# sensor.net
KiCad netlist of a schematic drawn in EAGLE
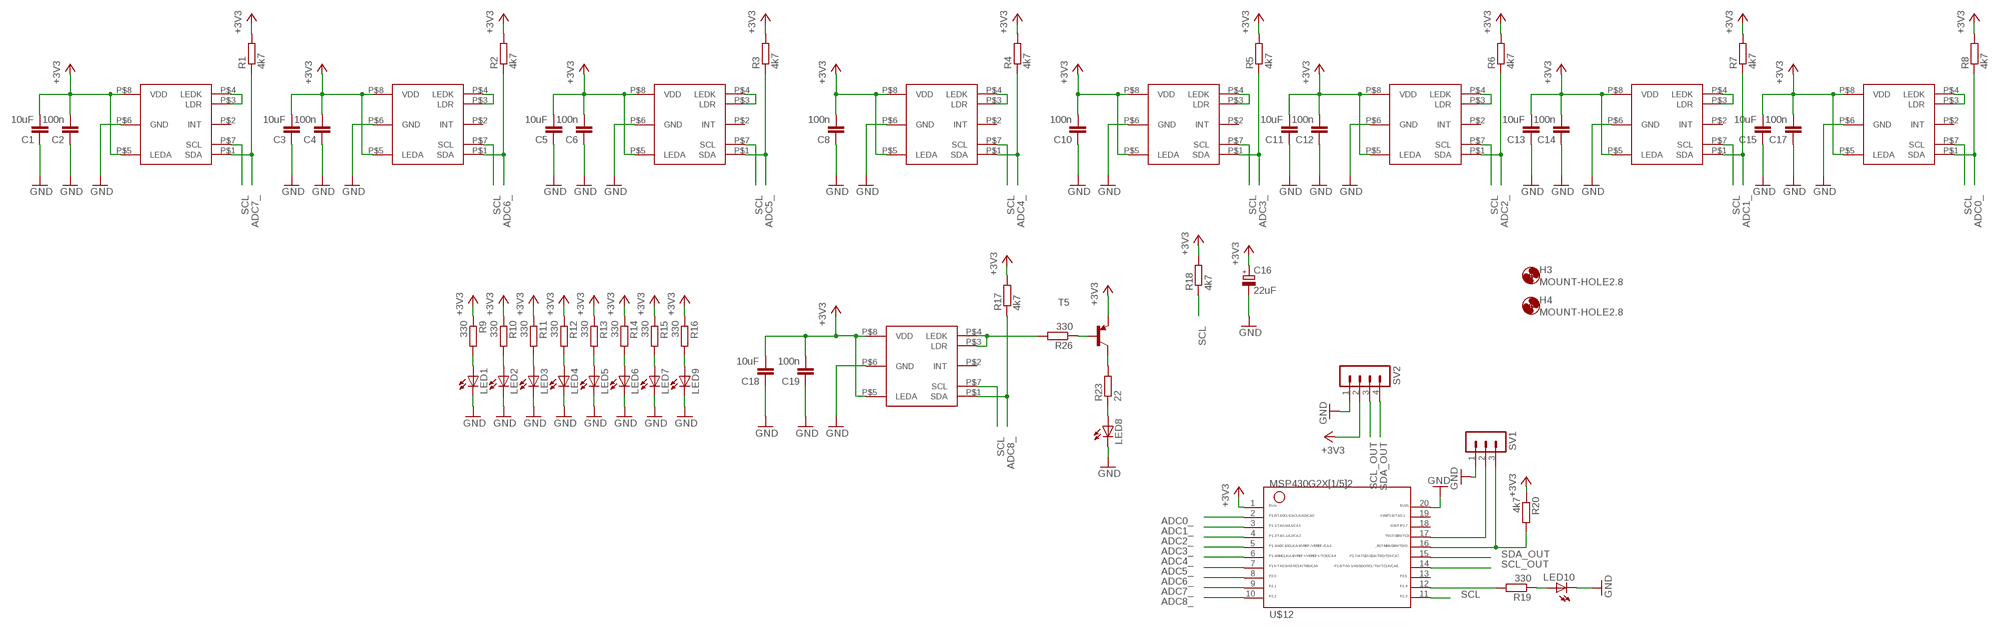
[diagram p0: schematic, sheet 1]

(export (version "E")
  (design (tool "Eeschema 10.0.6"))
  (components
    (comp (ref "C1")
      (value "10uF")
      (footprint "eagle-import:C0805")
      (libsource (lib "eagle-import") (part "C-EUC0805"))
    )
    (comp (ref "C2")
      (value "100n")
      (footprint "eagle-import:C0805")
      (libsource (lib "eagle-import") (part "C-EUC0805"))
    )
    (comp (ref "C3")
      (value "10uF")
      (footprint "eagle-import:C0805")
      (libsource (lib "eagle-import") (part "C-EUC0805"))
    )
    (comp (ref "C4")
      (value "100n")
      (footprint "eagle-import:C0805")
      (libsource (lib "eagle-import") (part "C-EUC0805"))
    )
    (comp (ref "C5")
      (value "10uF")
      (footprint "eagle-import:C0805")
      (libsource (lib "eagle-import") (part "C-EUC0805"))
    )
    (comp (ref "C6")
      (value "100n")
      (footprint "eagle-import:C0805")
      (libsource (lib "eagle-import") (part "C-EUC0805"))
    )
    (comp (ref "C8")
      (value "100n")
      (footprint "eagle-import:C0805")
      (libsource (lib "eagle-import") (part "C-EUC0805"))
    )
    (comp (ref "C10")
      (value "100n")
      (footprint "eagle-import:C0805")
      (libsource (lib "eagle-import") (part "C-EUC0805"))
    )
    (comp (ref "C11")
      (value "10uF")
      (footprint "eagle-import:C0805")
      (libsource (lib "eagle-import") (part "C-EUC0805"))
    )
    (comp (ref "C12")
      (value "100n")
      (footprint "eagle-import:C0805")
      (libsource (lib "eagle-import") (part "C-EUC0805"))
    )
    (comp (ref "C13")
      (value "10uF")
      (footprint "eagle-import:C0805")
      (libsource (lib "eagle-import") (part "C-EUC0805"))
    )
    (comp (ref "C14")
      (value "100n")
      (footprint "eagle-import:C0805")
      (libsource (lib "eagle-import") (part "C-EUC0805"))
    )
    (comp (ref "C15")
      (value "10uF")
      (footprint "eagle-import:C0805")
      (libsource (lib "eagle-import") (part "C-EUC0805"))
    )
    (comp (ref "C16")
      (value "22uF")
      (footprint "eagle-import:153CLV-0505")
      (libsource (lib "eagle-import") (part "CPOL-EU153CLV-0505"))
    )
    (comp (ref "C17")
      (value "100n")
      (footprint "eagle-import:C0805")
      (libsource (lib "eagle-import") (part "C-EUC0805"))
    )
    (comp (ref "C18")
      (value "10uF")
      (footprint "eagle-import:C0805")
      (libsource (lib "eagle-import") (part "C-EUC0805"))
    )
    (comp (ref "C19")
      (value "100n")
      (footprint "eagle-import:C0805")
      (libsource (lib "eagle-import") (part "C-EUC0805"))
    )
    (comp (ref "H3")
      (value "MOUNT-HOLE2.8")
      (footprint "eagle-import:2,8")
      (libsource (lib "eagle-import") (part "MOUNT-HOLE2.8"))
    )
    (comp (ref "H4")
      (value "MOUNT-HOLE2.8")
      (footprint "eagle-import:2,8")
      (libsource (lib "eagle-import") (part "MOUNT-HOLE2.8"))
    )
    (comp (ref "LED1")
      (value "LEDCHIPLED_1206")
      (footprint "eagle-import:CHIPLED_1206")
      (libsource (lib "eagle-import") (part "my_parts_LEDCHIPLED_1206"))
    )
    (comp (ref "LED2")
      (value "LEDCHIPLED_1206")
      (footprint "eagle-import:CHIPLED_1206")
      (libsource (lib "eagle-import") (part "my_parts_LEDCHIPLED_1206"))
    )
    (comp (ref "LED3")
      (value "LEDCHIPLED_1206")
      (footprint "eagle-import:CHIPLED_1206")
      (libsource (lib "eagle-import") (part "my_parts_LEDCHIPLED_1206"))
    )
    (comp (ref "LED4")
      (value "LEDCHIPLED_1206")
      (footprint "eagle-import:CHIPLED_1206")
      (libsource (lib "eagle-import") (part "my_parts_LEDCHIPLED_1206"))
    )
    (comp (ref "LED5")
      (value "LEDCHIPLED_1206")
      (footprint "eagle-import:CHIPLED_1206")
      (libsource (lib "eagle-import") (part "my_parts_LEDCHIPLED_1206"))
    )
    (comp (ref "LED6")
      (value "LEDCHIPLED_1206")
      (footprint "eagle-import:CHIPLED_1206")
      (libsource (lib "eagle-import") (part "my_parts_LEDCHIPLED_1206"))
    )
    (comp (ref "LED7")
      (value "LEDCHIPLED_1206")
      (footprint "eagle-import:CHIPLED_1206")
      (libsource (lib "eagle-import") (part "my_parts_LEDCHIPLED_1206"))
    )
    (comp (ref "LED8")
      (value "LED5MM")
      (footprint "eagle-import:LED5MM")
      (libsource (lib "eagle-import") (part "LED5MM"))
    )
    (comp (ref "LED9")
      (value "LEDCHIPLED_1206")
      (footprint "eagle-import:CHIPLED_1206")
      (libsource (lib "eagle-import") (part "my_parts_LEDCHIPLED_1206"))
    )
    (comp (ref "LED10")
      (value "LEDCHIPLED_1206")
      (footprint "eagle-import:CHIPLED_1206")
      (libsource (lib "eagle-import") (part "my_parts_LEDCHIPLED_1206"))
    )
    (comp (ref "R1")
      (value "4k7")
      (footprint "eagle-import:M0805")
      (libsource (lib "eagle-import") (part "R-EU_M0805"))
    )
    (comp (ref "R2")
      (value "4k7")
      (footprint "eagle-import:M0805")
      (libsource (lib "eagle-import") (part "R-EU_M0805"))
    )
    (comp (ref "R3")
      (value "4k7")
      (footprint "eagle-import:M0805")
      (libsource (lib "eagle-import") (part "R-EU_M0805"))
    )
    (comp (ref "R4")
      (value "4k7")
      (footprint "eagle-import:M0805")
      (libsource (lib "eagle-import") (part "R-EU_M0805"))
    )
    (comp (ref "R5")
      (value "4k7")
      (footprint "eagle-import:M0805")
      (libsource (lib "eagle-import") (part "R-EU_M0805"))
    )
    (comp (ref "R6")
      (value "4k7")
      (footprint "eagle-import:M0805")
      (libsource (lib "eagle-import") (part "R-EU_M0805"))
    )
    (comp (ref "R7")
      (value "4k7")
      (footprint "eagle-import:M0805")
      (libsource (lib "eagle-import") (part "R-EU_M0805"))
    )
    (comp (ref "R8")
      (value "4k7")
      (footprint "eagle-import:M0805")
      (libsource (lib "eagle-import") (part "R-EU_M0805"))
    )
    (comp (ref "R9")
      (value "330")
      (footprint "eagle-import:M0805")
      (libsource (lib "eagle-import") (part "R-EU_M0805"))
    )
    (comp (ref "R10")
      (value "330")
      (footprint "eagle-import:M0805")
      (libsource (lib "eagle-import") (part "R-EU_M0805"))
    )
    (comp (ref "R11")
      (value "330")
      (footprint "eagle-import:M0805")
      (libsource (lib "eagle-import") (part "R-EU_M0805"))
    )
    (comp (ref "R12")
      (value "330")
      (footprint "eagle-import:M0805")
      (libsource (lib "eagle-import") (part "R-EU_M0805"))
    )
    (comp (ref "R13")
      (value "330")
      (footprint "eagle-import:M0805")
      (libsource (lib "eagle-import") (part "R-EU_M0805"))
    )
    (comp (ref "R14")
      (value "330")
      (footprint "eagle-import:M0805")
      (libsource (lib "eagle-import") (part "R-EU_M0805"))
    )
    (comp (ref "R15")
      (value "330")
      (footprint "eagle-import:M0805")
      (libsource (lib "eagle-import") (part "R-EU_M0805"))
    )
    (comp (ref "R16")
      (value "330")
      (footprint "eagle-import:M0805")
      (libsource (lib "eagle-import") (part "R-EU_M0805"))
    )
    (comp (ref "R17")
      (value "4k7")
      (footprint "eagle-import:M0805")
      (libsource (lib "eagle-import") (part "R-EU_M0805"))
    )
    (comp (ref "R18")
      (value "4k7")
      (footprint "eagle-import:M0805")
      (libsource (lib "eagle-import") (part "R-EU_M0805"))
    )
    (comp (ref "R19")
      (value "330")
      (footprint "eagle-import:M0805")
      (libsource (lib "eagle-import") (part "R-EU_M0805"))
    )
    (comp (ref "R20")
      (value "4k7")
      (footprint "eagle-import:M0805")
      (libsource (lib "eagle-import") (part "R-EU_M0805"))
    )
    (comp (ref "R23")
      (value "22")
      (footprint "eagle-import:M0805")
      (libsource (lib "eagle-import") (part "R-EU_M0805"))
    )
    (comp (ref "R26")
      (value "330")
      (footprint "eagle-import:M0805")
      (libsource (lib "eagle-import") (part "R-EU_M0805"))
    )
    (comp (ref "SV1")
      (value "MA03-1")
      (footprint "eagle-import:MA03-1")
      (libsource (lib "eagle-import") (part "MA03-1"))
    )
    (comp (ref "SV2")
      (value "MA04-1")
      (footprint "eagle-import:MA04-1")
      (libsource (lib "eagle-import") (part "MA04-1"))
    )
    (comp (ref "T5")
      (value "BC857A-PNP-SOT23-BEC")
      (footprint "eagle-import:SOT23-BEC")
      (libsource (lib "eagle-import") (part "-PNP-SOT23-BECBC857A"))
    )
    (comp (ref "U$1")
      (value "APDS9950")
      (footprint "eagle-import:APDS9950")
      (libsource (lib "eagle-import") (part "APDS9950"))
    )
    (comp (ref "U$2")
      (value "APDS9950_EDGE")
      (footprint "eagle-import:APDS9950_EDGE")
      (libsource (lib "eagle-import") (part "APDS9950_EDGE"))
    )
    (comp (ref "U$4")
      (value "APDS9950")
      (footprint "eagle-import:APDS9950")
      (libsource (lib "eagle-import") (part "APDS9950"))
    )
    (comp (ref "U$5")
      (value "APDS9950")
      (footprint "eagle-import:APDS9950")
      (libsource (lib "eagle-import") (part "APDS9950"))
    )
    (comp (ref "U$6")
      (value "APDS9950")
      (footprint "eagle-import:APDS9950")
      (libsource (lib "eagle-import") (part "APDS9950"))
    )
    (comp (ref "U$7")
      (value "APDS9950")
      (footprint "eagle-import:APDS9950")
      (libsource (lib "eagle-import") (part "APDS9950"))
    )
    (comp (ref "U$8")
      (value "APDS9950")
      (footprint "eagle-import:APDS9950")
      (libsource (lib "eagle-import") (part "APDS9950"))
    )
    (comp (ref "U$9")
      (value "APDS9950")
      (footprint "eagle-import:APDS9950")
      (libsource (lib "eagle-import") (part "APDS9950"))
    )
    (comp (ref "U$10")
      (value "APDS9950")
      (footprint "eagle-import:APDS9950")
      (libsource (lib "eagle-import") (part "APDS9950"))
    )
    (comp (ref "U$12")
      (value "G2X[1/5]2---PW20")
      (footprint "eagle-import:PW20")
      (libsource (lib "eagle-import") (part "G2X[1/5]2---PW20"))
    )
  )
  (nets
    (net (code "1") (name "+3V3") (class "Default")
      (node (ref "C1") (pin "2") (pinfunction "2_2") (pintype "passive"))
      (node (ref "C10") (pin "2") (pinfunction "2_2") (pintype "passive"))
      (node (ref "C11") (pin "2") (pinfunction "2_2") (pintype "passive"))
      (node (ref "C12") (pin "2") (pinfunction "2_2") (pintype "passive"))
      (node (ref "C13") (pin "2") (pinfunction "2_2") (pintype "passive"))
      (node (ref "C14") (pin "2") (pinfunction "2_2") (pintype "passive"))
      (node (ref "C15") (pin "2") (pinfunction "2_2") (pintype "passive"))
      (node (ref "C16") (pin "+") (pinfunction "+_+") (pintype "passive"))
      (node (ref "C17") (pin "2") (pinfunction "2_2") (pintype "passive"))
      (node (ref "C18") (pin "2") (pinfunction "2_2") (pintype "passive"))
      (node (ref "C19") (pin "2") (pinfunction "2_2") (pintype "passive"))
      (node (ref "C2") (pin "2") (pinfunction "2_2") (pintype "passive"))
      (node (ref "C3") (pin "2") (pinfunction "2_2") (pintype "passive"))
      (node (ref "C4") (pin "2") (pinfunction "2_2") (pintype "passive"))
      (node (ref "C5") (pin "2") (pinfunction "2_2") (pintype "passive"))
      (node (ref "C6") (pin "2") (pinfunction "2_2") (pintype "passive"))
      (node (ref "C8") (pin "2") (pinfunction "2_2") (pintype "passive"))
      (node (ref "R1") (pin "2") (pinfunction "2_2") (pintype "passive"))
      (node (ref "R10") (pin "1") (pinfunction "1_1") (pintype "passive"))
      (node (ref "R11") (pin "1") (pinfunction "1_1") (pintype "passive"))
      (node (ref "R12") (pin "1") (pinfunction "1_1") (pintype "passive"))
      (node (ref "R13") (pin "1") (pinfunction "1_1") (pintype "passive"))
      (node (ref "R14") (pin "1") (pinfunction "1_1") (pintype "passive"))
      (node (ref "R15") (pin "1") (pinfunction "1_1") (pintype "passive"))
      (node (ref "R16") (pin "1") (pinfunction "1_1") (pintype "passive"))
      (node (ref "R17") (pin "2") (pinfunction "2_2") (pintype "passive"))
      (node (ref "R18") (pin "2") (pinfunction "2_2") (pintype "passive"))
      (node (ref "R2") (pin "2") (pinfunction "2_2") (pintype "passive"))
      (node (ref "R20") (pin "1") (pinfunction "1_1") (pintype "passive"))
      (node (ref "R3") (pin "2") (pinfunction "2_2") (pintype "passive"))
      (node (ref "R4") (pin "2") (pinfunction "2_2") (pintype "passive"))
      (node (ref "R5") (pin "2") (pinfunction "2_2") (pintype "passive"))
      (node (ref "R6") (pin "2") (pinfunction "2_2") (pintype "passive"))
      (node (ref "R7") (pin "2") (pinfunction "2_2") (pintype "passive"))
      (node (ref "R8") (pin "2") (pinfunction "2_2") (pintype "passive"))
      (node (ref "R9") (pin "1") (pinfunction "1_1") (pintype "passive"))
      (node (ref "SV2") (pin "2") (pinfunction "2_2") (pintype "passive"))
      (node (ref "T5") (pin "E") (pinfunction "E_E") (pintype "passive"))
      (node (ref "U$1") (pin "P$5") (pinfunction "LEDA_P$5") (pintype "bidirectional"))
      (node (ref "U$1") (pin "P$8") (pinfunction "VDD_P$8") (pintype "bidirectional"))
      (node (ref "U$10") (pin "P$5") (pinfunction "LEDA_P$5") (pintype "bidirectional"))
      (node (ref "U$10") (pin "P$8") (pinfunction "VDD_P$8") (pintype "bidirectional"))
      (node (ref "U$12") (pin "1") (pinfunction "1_1") (pintype "bidirectional"))
      (node (ref "U$2") (pin "P$5") (pinfunction "LEDA_P$5") (pintype "bidirectional"))
      (node (ref "U$2") (pin "P$8") (pinfunction "VDD_P$8") (pintype "bidirectional"))
      (node (ref "U$4") (pin "P$5") (pinfunction "LEDA_P$5") (pintype "bidirectional"))
      (node (ref "U$4") (pin "P$8") (pinfunction "VDD_P$8") (pintype "bidirectional"))
      (node (ref "U$5") (pin "P$5") (pinfunction "LEDA_P$5") (pintype "bidirectional"))
      (node (ref "U$5") (pin "P$8") (pinfunction "VDD_P$8") (pintype "bidirectional"))
      (node (ref "U$6") (pin "P$5") (pinfunction "LEDA_P$5") (pintype "bidirectional"))
      (node (ref "U$6") (pin "P$8") (pinfunction "VDD_P$8") (pintype "bidirectional"))
      (node (ref "U$7") (pin "P$5") (pinfunction "LEDA_P$5") (pintype "bidirectional"))
      (node (ref "U$7") (pin "P$8") (pinfunction "VDD_P$8") (pintype "bidirectional"))
      (node (ref "U$8") (pin "P$5") (pinfunction "LEDA_P$5") (pintype "bidirectional"))
      (node (ref "U$8") (pin "P$8") (pinfunction "VDD_P$8") (pintype "bidirectional"))
      (node (ref "U$9") (pin "P$5") (pinfunction "LEDA_P$5") (pintype "bidirectional"))
      (node (ref "U$9") (pin "P$8") (pinfunction "VDD_P$8") (pintype "bidirectional"))
    )
    (net (code "2") (name "/ADC0_") (class "Default")
      (node (ref "R8") (pin "1") (pinfunction "1_1") (pintype "passive"))
      (node (ref "U$10") (pin "P$1") (pinfunction "SDA_P$1") (pintype "bidirectional"))
      (node (ref "U$12") (pin "2") (pinfunction "2_2") (pintype "bidirectional"))
    )
    (net (code "3") (name "/ADC1_") (class "Default")
      (node (ref "R7") (pin "1") (pinfunction "1_1") (pintype "passive"))
      (node (ref "U$12") (pin "3") (pinfunction "3_3") (pintype "bidirectional"))
      (node (ref "U$9") (pin "P$1") (pinfunction "SDA_P$1") (pintype "bidirectional"))
    )
    (net (code "4") (name "/ADC2_") (class "Default")
      (node (ref "R6") (pin "1") (pinfunction "1_1") (pintype "passive"))
      (node (ref "U$12") (pin "4") (pinfunction "4_4") (pintype "bidirectional"))
      (node (ref "U$8") (pin "P$1") (pinfunction "SDA_P$1") (pintype "bidirectional"))
    )
    (net (code "5") (name "/ADC3_") (class "Default")
      (node (ref "R5") (pin "1") (pinfunction "1_1") (pintype "passive"))
      (node (ref "U$12") (pin "5") (pinfunction "5_5") (pintype "bidirectional"))
      (node (ref "U$7") (pin "P$1") (pinfunction "SDA_P$1") (pintype "bidirectional"))
    )
    (net (code "6") (name "/ADC4_") (class "Default")
      (node (ref "R4") (pin "1") (pinfunction "1_1") (pintype "passive"))
      (node (ref "U$12") (pin "6") (pinfunction "6_6") (pintype "bidirectional"))
      (node (ref "U$6") (pin "P$1") (pinfunction "SDA_P$1") (pintype "bidirectional"))
    )
    (net (code "7") (name "/ADC5_") (class "Default")
      (node (ref "R3") (pin "1") (pinfunction "1_1") (pintype "passive"))
      (node (ref "U$12") (pin "7") (pinfunction "7_7") (pintype "bidirectional"))
      (node (ref "U$5") (pin "P$1") (pinfunction "SDA_P$1") (pintype "bidirectional"))
    )
    (net (code "8") (name "/ADC6_") (class "Default")
      (node (ref "R2") (pin "1") (pinfunction "1_1") (pintype "passive"))
      (node (ref "U$12") (pin "8") (pinfunction "8_8") (pintype "bidirectional"))
      (node (ref "U$4") (pin "P$1") (pinfunction "SDA_P$1") (pintype "bidirectional"))
    )
    (net (code "9") (name "/ADC7_") (class "Default")
      (node (ref "R1") (pin "1") (pinfunction "1_1") (pintype "passive"))
      (node (ref "U$1") (pin "P$1") (pinfunction "SDA_P$1") (pintype "bidirectional"))
      (node (ref "U$12") (pin "9") (pinfunction "9_9") (pintype "bidirectional"))
    )
    (net (code "10") (name "/ADC8_") (class "Default")
      (node (ref "R17") (pin "1") (pinfunction "1_1") (pintype "passive"))
      (node (ref "U$12") (pin "10") (pinfunction "10_10") (pintype "bidirectional"))
      (node (ref "U$2") (pin "P$1") (pinfunction "SDA_P$1") (pintype "bidirectional"))
    )
    (net (code "11") (name "/SCL") (class "Default")
      (node (ref "R18") (pin "1") (pinfunction "1_1") (pintype "passive"))
      (node (ref "U$1") (pin "P$7") (pinfunction "SCL_P$7") (pintype "bidirectional"))
      (node (ref "U$10") (pin "P$7") (pinfunction "SCL_P$7") (pintype "bidirectional"))
      (node (ref "U$12") (pin "11") (pinfunction "11_11") (pintype "bidirectional"))
      (node (ref "U$2") (pin "P$7") (pinfunction "SCL_P$7") (pintype "bidirectional"))
      (node (ref "U$4") (pin "P$7") (pinfunction "SCL_P$7") (pintype "bidirectional"))
      (node (ref "U$5") (pin "P$7") (pinfunction "SCL_P$7") (pintype "bidirectional"))
      (node (ref "U$6") (pin "P$7") (pinfunction "SCL_P$7") (pintype "bidirectional"))
      (node (ref "U$7") (pin "P$7") (pinfunction "SCL_P$7") (pintype "bidirectional"))
      (node (ref "U$8") (pin "P$7") (pinfunction "SCL_P$7") (pintype "bidirectional"))
      (node (ref "U$9") (pin "P$7") (pinfunction "SCL_P$7") (pintype "bidirectional"))
    )
    (net (code "12") (name "/SCL_OUT") (class "Default")
      (node (ref "SV2") (pin "3") (pinfunction "3_3") (pintype "passive"))
      (node (ref "U$12") (pin "14") (pinfunction "14_14") (pintype "bidirectional"))
    )
    (net (code "13") (name "/SDA_OUT") (class "Default")
      (node (ref "SV2") (pin "4") (pinfunction "4_4") (pintype "passive"))
      (node (ref "U$12") (pin "15") (pinfunction "15_15") (pintype "bidirectional"))
    )
    (net (code "14") (name "GND") (class "Default")
      (node (ref "C1") (pin "1") (pinfunction "1_1") (pintype "passive"))
      (node (ref "C10") (pin "1") (pinfunction "1_1") (pintype "passive"))
      (node (ref "C11") (pin "1") (pinfunction "1_1") (pintype "passive"))
      (node (ref "C12") (pin "1") (pinfunction "1_1") (pintype "passive"))
      (node (ref "C13") (pin "1") (pinfunction "1_1") (pintype "passive"))
      (node (ref "C14") (pin "1") (pinfunction "1_1") (pintype "passive"))
      (node (ref "C15") (pin "1") (pinfunction "1_1") (pintype "passive"))
      (node (ref "C16") (pin "-") (pinfunction "-_-") (pintype "passive"))
      (node (ref "C17") (pin "1") (pinfunction "1_1") (pintype "passive"))
      (node (ref "C18") (pin "1") (pinfunction "1_1") (pintype "passive"))
      (node (ref "C19") (pin "1") (pinfunction "1_1") (pintype "passive"))
      (node (ref "C2") (pin "1") (pinfunction "1_1") (pintype "passive"))
      (node (ref "C3") (pin "1") (pinfunction "1_1") (pintype "passive"))
      (node (ref "C4") (pin "1") (pinfunction "1_1") (pintype "passive"))
      (node (ref "C5") (pin "1") (pinfunction "1_1") (pintype "passive"))
      (node (ref "C6") (pin "1") (pinfunction "1_1") (pintype "passive"))
      (node (ref "C8") (pin "1") (pinfunction "1_1") (pintype "passive"))
      (node (ref "LED1") (pin "C") (pinfunction "C_C") (pintype "passive"))
      (node (ref "LED10") (pin "C") (pinfunction "C_C") (pintype "passive"))
      (node (ref "LED2") (pin "C") (pinfunction "C_C") (pintype "passive"))
      (node (ref "LED3") (pin "C") (pinfunction "C_C") (pintype "passive"))
      (node (ref "LED4") (pin "C") (pinfunction "C_C") (pintype "passive"))
      (node (ref "LED5") (pin "C") (pinfunction "C_C") (pintype "passive"))
      (node (ref "LED6") (pin "C") (pinfunction "C_C") (pintype "passive"))
      (node (ref "LED7") (pin "C") (pinfunction "C_C") (pintype "passive"))
      (node (ref "LED8") (pin "K") (pinfunction "C_K") (pintype "passive"))
      (node (ref "LED9") (pin "C") (pinfunction "C_C") (pintype "passive"))
      (node (ref "SV1") (pin "1") (pinfunction "1_1") (pintype "passive"))
      (node (ref "SV2") (pin "1") (pinfunction "1_1") (pintype "passive"))
      (node (ref "U$1") (pin "P$6") (pinfunction "GND_P$6") (pintype "bidirectional"))
      (node (ref "U$10") (pin "P$6") (pinfunction "GND_P$6") (pintype "bidirectional"))
      (node (ref "U$12") (pin "20") (pinfunction "20_20") (pintype "bidirectional"))
      (node (ref "U$2") (pin "P$6") (pinfunction "GND_P$6") (pintype "bidirectional"))
      (node (ref "U$4") (pin "P$6") (pinfunction "GND_P$6") (pintype "bidirectional"))
      (node (ref "U$5") (pin "P$6") (pinfunction "GND_P$6") (pintype "bidirectional"))
      (node (ref "U$6") (pin "P$6") (pinfunction "GND_P$6") (pintype "bidirectional"))
      (node (ref "U$7") (pin "P$6") (pinfunction "GND_P$6") (pintype "bidirectional"))
      (node (ref "U$8") (pin "P$6") (pinfunction "GND_P$6") (pintype "bidirectional"))
      (node (ref "U$9") (pin "P$6") (pinfunction "GND_P$6") (pintype "bidirectional"))
    )
    (net (code "15") (name "Net-(LED1-PadA)") (class "Default")
      (node (ref "LED1") (pin "A") (pinfunction "A_A") (pintype "passive"))
      (node (ref "R9") (pin "2") (pinfunction "2_2") (pintype "passive"))
    )
    (net (code "16") (name "Net-(LED2-PadA)") (class "Default")
      (node (ref "LED2") (pin "A") (pinfunction "A_A") (pintype "passive"))
      (node (ref "R10") (pin "2") (pinfunction "2_2") (pintype "passive"))
    )
    (net (code "17") (name "Net-(LED3-PadA)") (class "Default")
      (node (ref "LED3") (pin "A") (pinfunction "A_A") (pintype "passive"))
      (node (ref "R11") (pin "2") (pinfunction "2_2") (pintype "passive"))
    )
    (net (code "18") (name "Net-(LED4-PadA)") (class "Default")
      (node (ref "LED4") (pin "A") (pinfunction "A_A") (pintype "passive"))
      (node (ref "R12") (pin "2") (pinfunction "2_2") (pintype "passive"))
    )
    (net (code "19") (name "Net-(LED5-PadA)") (class "Default")
      (node (ref "LED5") (pin "A") (pinfunction "A_A") (pintype "passive"))
      (node (ref "R13") (pin "2") (pinfunction "2_2") (pintype "passive"))
    )
    (net (code "20") (name "Net-(LED6-PadA)") (class "Default")
      (node (ref "LED6") (pin "A") (pinfunction "A_A") (pintype "passive"))
      (node (ref "R14") (pin "2") (pinfunction "2_2") (pintype "passive"))
    )
    (net (code "21") (name "Net-(LED7-PadA)") (class "Default")
      (node (ref "LED7") (pin "A") (pinfunction "A_A") (pintype "passive"))
      (node (ref "R15") (pin "2") (pinfunction "2_2") (pintype "passive"))
    )
    (net (code "22") (name "Net-(LED8-PadA)") (class "Default")
      (node (ref "LED8") (pin "A") (pinfunction "A_A") (pintype "passive"))
      (node (ref "R23") (pin "1") (pinfunction "1_1") (pintype "passive"))
    )
    (net (code "23") (name "Net-(LED9-PadA)") (class "Default")
      (node (ref "LED9") (pin "A") (pinfunction "A_A") (pintype "passive"))
      (node (ref "R16") (pin "2") (pinfunction "2_2") (pintype "passive"))
    )
    (net (code "24") (name "Net-(LED10-PadA)") (class "Default")
      (node (ref "LED10") (pin "A") (pinfunction "A_A") (pintype "passive"))
      (node (ref "R19") (pin "1") (pinfunction "1_1") (pintype "passive"))
    )
    (net (code "25") (name "Net-(R19-Pad2)") (class "Default")
      (node (ref "R19") (pin "2") (pinfunction "2_2") (pintype "passive"))
      (node (ref "U$12") (pin "12") (pinfunction "12_12") (pintype "bidirectional"))
    )
    (net (code "26") (name "Net-(R20-Pad2)") (class "Default")
      (node (ref "R20") (pin "2") (pinfunction "2_2") (pintype "passive"))
      (node (ref "SV1") (pin "3") (pinfunction "3_3") (pintype "passive"))
      (node (ref "U$12") (pin "16") (pinfunction "16_16") (pintype "bidirectional"))
    )
    (net (code "27") (name "Net-(R23-Pad2)") (class "Default")
      (node (ref "R23") (pin "2") (pinfunction "2_2") (pintype "passive"))
      (node (ref "T5") (pin "C") (pinfunction "C_C") (pintype "passive"))
    )
    (net (code "28") (name "Net-(R26-Pad1)") (class "Default")
      (node (ref "R26") (pin "1") (pinfunction "1_1") (pintype "passive"))
      (node (ref "T5") (pin "B") (pinfunction "B_B") (pintype "passive"))
    )
    (net (code "29") (name "Net-(SV1-Pad2)") (class "Default")
      (node (ref "SV1") (pin "2") (pinfunction "2_2") (pintype "passive"))
      (node (ref "U$12") (pin "17") (pinfunction "17_17") (pintype "bidirectional"))
    )
    (net (code "30") (name "Net-(U$1-LDR)") (class "Default")
      (node (ref "U$1") (pin "P$3") (pinfunction "LDR_P$3") (pintype "bidirectional"))
      (node (ref "U$1") (pin "P$4") (pinfunction "LEDK_P$4") (pintype "bidirectional"))
    )
    (net (code "31") (name "Net-(U$2-LDR)") (class "Default")
      (node (ref "R26") (pin "2") (pinfunction "2_2") (pintype "passive"))
      (node (ref "U$2") (pin "P$3") (pinfunction "LDR_P$3") (pintype "bidirectional"))
      (node (ref "U$2") (pin "P$4") (pinfunction "LEDK_P$4") (pintype "bidirectional"))
    )
    (net (code "32") (name "Net-(U$4-LDR)") (class "Default")
      (node (ref "U$4") (pin "P$3") (pinfunction "LDR_P$3") (pintype "bidirectional"))
      (node (ref "U$4") (pin "P$4") (pinfunction "LEDK_P$4") (pintype "bidirectional"))
    )
    (net (code "33") (name "Net-(U$5-LDR)") (class "Default")
      (node (ref "U$5") (pin "P$3") (pinfunction "LDR_P$3") (pintype "bidirectional"))
      (node (ref "U$5") (pin "P$4") (pinfunction "LEDK_P$4") (pintype "bidirectional"))
    )
    (net (code "34") (name "Net-(U$6-LDR)") (class "Default")
      (node (ref "U$6") (pin "P$3") (pinfunction "LDR_P$3") (pintype "bidirectional"))
      (node (ref "U$6") (pin "P$4") (pinfunction "LEDK_P$4") (pintype "bidirectional"))
    )
    (net (code "35") (name "Net-(U$7-LDR)") (class "Default")
      (node (ref "U$7") (pin "P$3") (pinfunction "LDR_P$3") (pintype "bidirectional"))
      (node (ref "U$7") (pin "P$4") (pinfunction "LEDK_P$4") (pintype "bidirectional"))
    )
    (net (code "36") (name "Net-(U$8-LDR)") (class "Default")
      (node (ref "U$8") (pin "P$3") (pinfunction "LDR_P$3") (pintype "bidirectional"))
      (node (ref "U$8") (pin "P$4") (pinfunction "LEDK_P$4") (pintype "bidirectional"))
    )
    (net (code "37") (name "Net-(U$9-LDR)") (class "Default")
      (node (ref "U$9") (pin "P$3") (pinfunction "LDR_P$3") (pintype "bidirectional"))
      (node (ref "U$9") (pin "P$4") (pinfunction "LEDK_P$4") (pintype "bidirectional"))
    )
    (net (code "38") (name "Net-(U$10-LDR)") (class "Default")
      (node (ref "U$10") (pin "P$3") (pinfunction "LDR_P$3") (pintype "bidirectional"))
      (node (ref "U$10") (pin "P$4") (pinfunction "LEDK_P$4") (pintype "bidirectional"))
    )
    (net (code "39") (name "unconnected-(U$1-INT-PadP$2)") (class "Default")
      (node (ref "U$1") (pin "P$2") (pinfunction "INT_P$2") (pintype "bidirectional"))
    )
    (net (code "40") (name "unconnected-(U$2-INT-PadP$2)") (class "Default")
      (node (ref "U$2") (pin "P$2") (pinfunction "INT_P$2") (pintype "bidirectional"))
    )
    (net (code "41") (name "unconnected-(U$4-INT-PadP$2)") (class "Default")
      (node (ref "U$4") (pin "P$2") (pinfunction "INT_P$2") (pintype "bidirectional"))
    )
    (net (code "42") (name "unconnected-(U$5-INT-PadP$2)") (class "Default")
      (node (ref "U$5") (pin "P$2") (pinfunction "INT_P$2") (pintype "bidirectional"))
    )
    (net (code "43") (name "unconnected-(U$6-INT-PadP$2)") (class "Default")
      (node (ref "U$6") (pin "P$2") (pinfunction "INT_P$2") (pintype "bidirectional"))
    )
    (net (code "44") (name "unconnected-(U$7-INT-PadP$2)") (class "Default")
      (node (ref "U$7") (pin "P$2") (pinfunction "INT_P$2") (pintype "bidirectional"))
    )
    (net (code "45") (name "unconnected-(U$8-INT-PadP$2)") (class "Default")
      (node (ref "U$8") (pin "P$2") (pinfunction "INT_P$2") (pintype "bidirectional"))
    )
    (net (code "46") (name "unconnected-(U$9-INT-PadP$2)") (class "Default")
      (node (ref "U$9") (pin "P$2") (pinfunction "INT_P$2") (pintype "bidirectional"))
    )
    (net (code "47") (name "unconnected-(U$10-INT-PadP$2)") (class "Default")
      (node (ref "U$10") (pin "P$2") (pinfunction "INT_P$2") (pintype "bidirectional"))
    )
    (net (code "48") (name "unconnected-(U$12-Pad13)") (class "Default")
      (node (ref "U$12") (pin "13") (pinfunction "13_13") (pintype "bidirectional"))
    )
    (net (code "49") (name "unconnected-(U$12-Pad18)") (class "Default")
      (node (ref "U$12") (pin "18") (pinfunction "18_18") (pintype "bidirectional"))
    )
    (net (code "50") (name "unconnected-(U$12-Pad19)") (class "Default")
      (node (ref "U$12") (pin "19") (pinfunction "19_19") (pintype "bidirectional"))
    )
  )
)
